# bf2_redraw.net
KiCad netlist of a schematic drawn in EAGLE
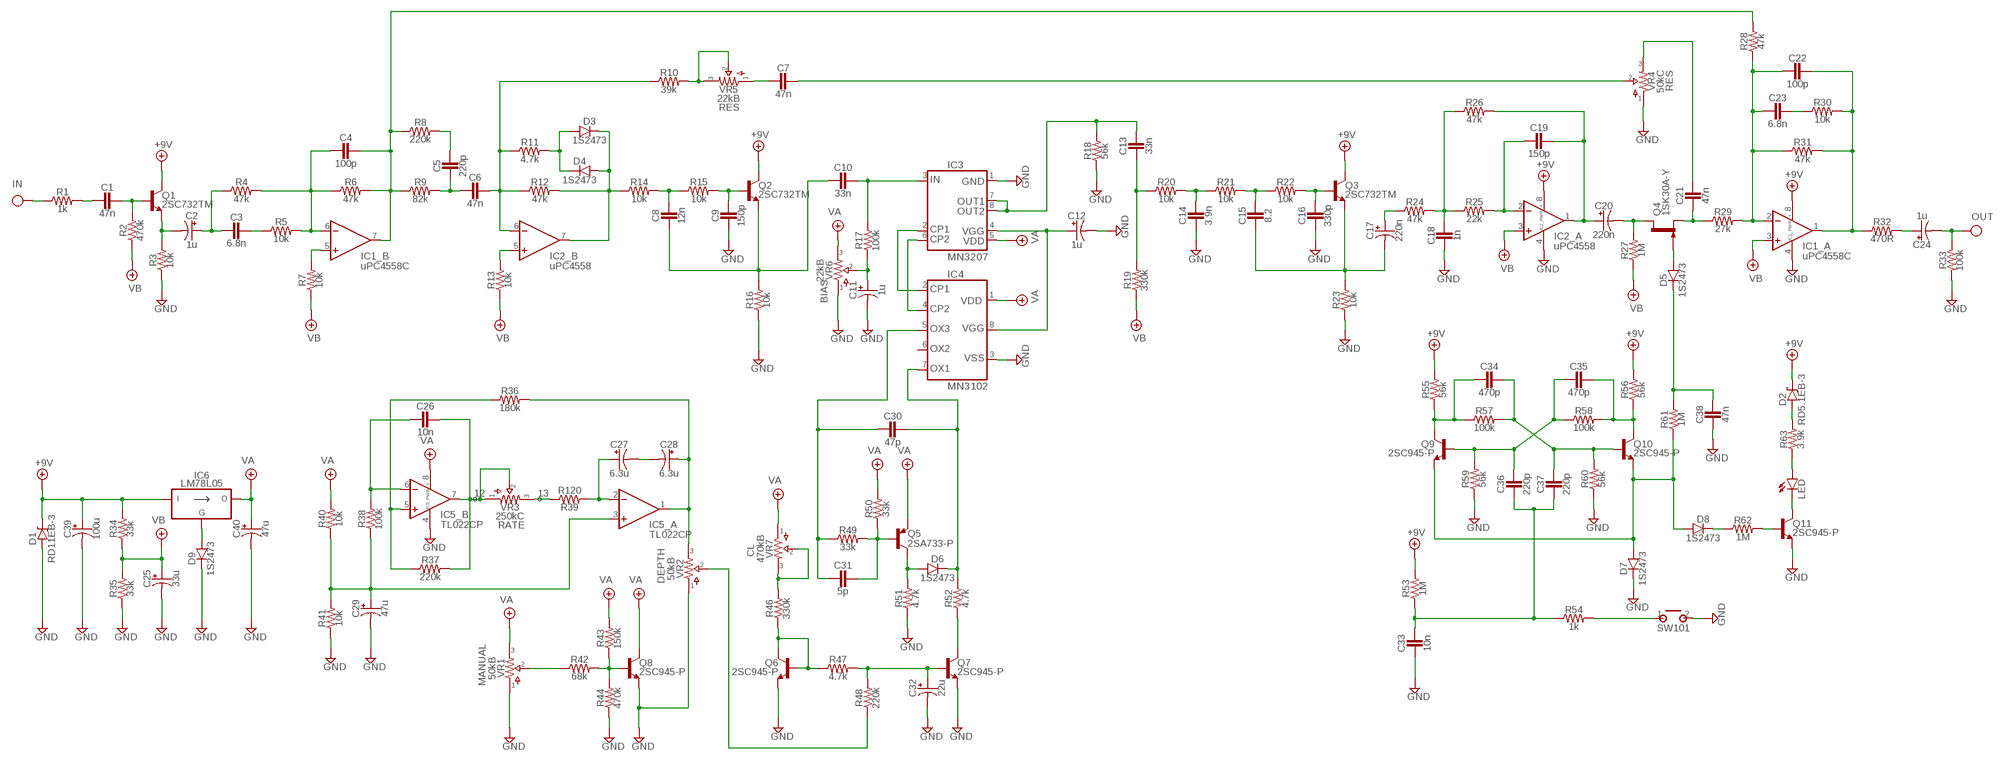
[diagram p0: schematic, sheet 1]

(export (version "E")
  (design (tool "Eeschema 10.0.6"))
  (components
    (comp (ref "C1")
      (value "47n")
      (footprint "eagle-import:BOX_SMALL")
      (libsource (lib "eagle-import") (part "CER/FILMBOX.1"))
    )
    (comp (ref "C2")
      (value "1u")
      (footprint "eagle-import:040_020")
      (libsource (lib "eagle-import") (part "0400"))
    )
    (comp (ref "C3")
      (value "6.8n")
      (footprint "eagle-import:BOX_SMALL")
      (libsource (lib "eagle-import") (part "CER/FILMBOX.1"))
    )
    (comp (ref "C4")
      (value "100p")
      (footprint "eagle-import:BOX_SMALL")
      (libsource (lib "eagle-import") (part "CER/FILMBOX.1"))
    )
    (comp (ref "C5")
      (value "220p")
      (footprint "eagle-import:BOX_SMALL")
      (libsource (lib "eagle-import") (part "CER/FILMBOX.1"))
    )
    (comp (ref "C6")
      (value "47n")
      (footprint "eagle-import:BOX_SMALL")
      (libsource (lib "eagle-import") (part "CER/FILMBOX.1"))
    )
    (comp (ref "C7")
      (value "47n")
      (footprint "eagle-import:BOX_SMALL")
      (libsource (lib "eagle-import") (part "CER/FILMBOX.1"))
    )
    (comp (ref "C8")
      (value "12n")
      (footprint "eagle-import:BOX_SMALL")
      (libsource (lib "eagle-import") (part "CER/FILMBOX.1"))
    )
    (comp (ref "C9")
      (value "150p")
      (footprint "eagle-import:BOX_SMALL")
      (libsource (lib "eagle-import") (part "CER/FILMBOX.1"))
    )
    (comp (ref "C10")
      (value "33n")
      (footprint "eagle-import:BOX_SMALL")
      (libsource (lib "eagle-import") (part "CER/FILMBOX.1"))
    )
    (comp (ref "C11")
      (value "1u")
      (footprint "eagle-import:040_020")
      (libsource (lib "eagle-import") (part "0400"))
    )
    (comp (ref "C12")
      (value "1u")
      (footprint "eagle-import:040_020")
      (libsource (lib "eagle-import") (part "0400"))
    )
    (comp (ref "C13")
      (value "33n")
      (footprint "eagle-import:BOX_SMALL")
      (libsource (lib "eagle-import") (part "CER/FILMBOX.1"))
    )
    (comp (ref "C14")
      (value "3.9n")
      (footprint "eagle-import:BOX_SMALL")
      (libsource (lib "eagle-import") (part "CER/FILMBOX.1"))
    )
    (comp (ref "C15")
      (value "8.2")
      (footprint "eagle-import:BOX_SMALL")
      (libsource (lib "eagle-import") (part "CER/FILMBOX.1"))
    )
    (comp (ref "C16")
      (value "330p")
      (footprint "eagle-import:BOX_SMALL")
      (libsource (lib "eagle-import") (part "CER/FILMBOX.1"))
    )
    (comp (ref "C17")
      (value "220n")
      (footprint "eagle-import:040_020")
      (libsource (lib "eagle-import") (part "0400"))
    )
    (comp (ref "C18")
      (value "1n")
      (footprint "eagle-import:BOX_SMALL")
      (libsource (lib "eagle-import") (part "CER/FILMBOX.1"))
    )
    (comp (ref "C19")
      (value "150p")
      (footprint "eagle-import:BOX_SMALL")
      (libsource (lib "eagle-import") (part "CER/FILMBOX.1"))
    )
    (comp (ref "C20")
      (value "220n")
      (footprint "eagle-import:040_020")
      (libsource (lib "eagle-import") (part "0400"))
    )
    (comp (ref "C21")
      (value "47n")
      (footprint "eagle-import:BOX_SMALL")
      (libsource (lib "eagle-import") (part "CER/FILMBOX.1"))
    )
    (comp (ref "C22")
      (value "100p")
      (footprint "eagle-import:BOX_SMALL")
      (libsource (lib "eagle-import") (part "CER/FILMBOX.1"))
    )
    (comp (ref "C23")
      (value "6.8n")
      (footprint "eagle-import:BOX_SMALL")
      (libsource (lib "eagle-import") (part "CER/FILMBOX.1"))
    )
    (comp (ref "C24")
      (value "1u")
      (footprint "eagle-import:040_020")
      (libsource (lib "eagle-import") (part "0400"))
    )
    (comp (ref "C25")
      (value "33u")
      (footprint "eagle-import:040_020")
      (libsource (lib "eagle-import") (part "0400"))
    )
    (comp (ref "C26")
      (value "10n")
      (footprint "eagle-import:BOX_SMALL")
      (libsource (lib "eagle-import") (part "CER/FILMBOX.1"))
    )
    (comp (ref "C27")
      (value "6.3u")
      (footprint "eagle-import:040_020")
      (libsource (lib "eagle-import") (part "0400"))
    )
    (comp (ref "C28")
      (value "6.3u")
      (footprint "eagle-import:040_020")
      (libsource (lib "eagle-import") (part "0400"))
    )
    (comp (ref "C29")
      (value "47u")
      (footprint "eagle-import:040_020")
      (libsource (lib "eagle-import") (part "0400"))
    )
    (comp (ref "C30")
      (value "47p")
      (footprint "eagle-import:BOX_SMALL")
      (libsource (lib "eagle-import") (part "CER/FILMBOX.1"))
    )
    (comp (ref "C31")
      (value "5p")
      (footprint "eagle-import:BOX_SMALL")
      (libsource (lib "eagle-import") (part "CER/FILMBOX.1"))
    )
    (comp (ref "C32")
      (value "22u")
      (footprint "eagle-import:040_020")
      (libsource (lib "eagle-import") (part "0400"))
    )
    (comp (ref "C33")
      (value "10n")
      (footprint "eagle-import:BOX_SMALL")
      (libsource (lib "eagle-import") (part "CER/FILMBOX.1"))
    )
    (comp (ref "C34")
      (value "470p")
      (footprint "eagle-import:BOX_SMALL")
      (libsource (lib "eagle-import") (part "CER/FILMBOX.1"))
    )
    (comp (ref "C35")
      (value "470p")
      (footprint "eagle-import:BOX_SMALL")
      (libsource (lib "eagle-import") (part "CER/FILMBOX.1"))
    )
    (comp (ref "C36")
      (value "220p")
      (footprint "eagle-import:BOX_SMALL")
      (libsource (lib "eagle-import") (part "CER/FILMBOX.1"))
    )
    (comp (ref "C37")
      (value "220p")
      (footprint "eagle-import:BOX_SMALL")
      (libsource (lib "eagle-import") (part "CER/FILMBOX.1"))
    )
    (comp (ref "C38")
      (value "47n")
      (footprint "eagle-import:BOX_SMALL")
      (libsource (lib "eagle-import") (part "CER/FILMBOX.1"))
    )
    (comp (ref "C39")
      (value "100u")
      (footprint "eagle-import:040_020")
      (libsource (lib "eagle-import") (part "0400"))
    )
    (comp (ref "C40")
      (value "47u")
      (footprint "eagle-import:040_020")
      (libsource (lib "eagle-import") (part "0400"))
    )
    (comp (ref "D1")
      (value "RD11EB-3")
      (footprint "eagle-import:DO41-2")
      (libsource (lib "eagle-import") (part "ZENER.2"))
    )
    (comp (ref "D2")
      (value "RD5.1EB-3")
      (footprint "eagle-import:DO41-2")
      (libsource (lib "eagle-import") (part "ZENER.2"))
    )
    (comp (ref "D3")
      (value "1S2473")
      (footprint "eagle-import:DO35-2")
      (libsource (lib "eagle-import") (part "DO35.2"))
    )
    (comp (ref "D4")
      (value "1S2473")
      (footprint "eagle-import:DO35-2")
      (libsource (lib "eagle-import") (part "DO35.2"))
    )
    (comp (ref "D5")
      (value "1S2473")
      (footprint "eagle-import:DO35-2")
      (libsource (lib "eagle-import") (part "DO35.2"))
    )
    (comp (ref "D6")
      (value "1S2473")
      (footprint "eagle-import:DO35-2")
      (libsource (lib "eagle-import") (part "DO35.2"))
    )
    (comp (ref "D7")
      (value "1S2473")
      (footprint "eagle-import:DO35-2")
      (libsource (lib "eagle-import") (part "DO35.2"))
    )
    (comp (ref "D8")
      (value "1S2473")
      (footprint "eagle-import:DO35-2")
      (libsource (lib "eagle-import") (part "DO35.2"))
    )
    (comp (ref "D9")
      (value "1S2473")
      (footprint "eagle-import:DO35-2")
      (libsource (lib "eagle-import") (part "DO35.2"))
    )
    (comp (ref "IC1")
      (value "uPC4558C")
      (footprint "eagle-import:DIL0")
      (libsource (lib "eagle-import") (part "DUALTH"))
    )
    (comp (ref "IC2")
      (value "uPC4558")
      (footprint "eagle-import:DIL0")
      (libsource (lib "eagle-import") (part "DUALTH"))
    )
    (comp (ref "IC3")
      (value "MN3207")
      (footprint "eagle-import:DIL0")
      (libsource (lib "eagle-import") (part "BL3208"))
    )
    (comp (ref "IC4")
      (value "MN3102")
      (footprint "eagle-import:DIL8")
      (libsource (lib "eagle-import") (part "CLOCK"))
    )
    (comp (ref "IC5")
      (value "TL022CP")
      (footprint "eagle-import:DIL0")
      (libsource (lib "eagle-import") (part "DUALTH"))
    )
    (comp (ref "IC6")
      (value "LM78L05")
      (footprint "eagle-import:TO92-")
      (libsource (lib "eagle-import") (part "LM78L05"))
    )
    (comp (ref "LED")
      (value "SLP1358")
      (footprint "eagle-import:3MM_D")
      (libsource (lib "eagle-import") (part "LED"))
    )
    (comp (ref "Q1")
      (value "2SC732TM")
      (footprint "eagle-import:TO92-")
      (libsource (lib "eagle-import") (part "2SC828A"))
    )
    (comp (ref "Q2")
      (value "2SC732TM")
      (footprint "eagle-import:TO92-")
      (libsource (lib "eagle-import") (part "2SC828A"))
    )
    (comp (ref "Q3")
      (value "2SC732TM")
      (footprint "eagle-import:TO92-")
      (libsource (lib "eagle-import") (part "2SC828A"))
    )
    (comp (ref "Q4")
      (value "1SK30A-Y")
      (footprint "eagle-import:TO92-")
      (libsource (lib "eagle-import") (part "2N3819TO-92S"))
    )
    (comp (ref "Q5")
      (value "2SA733-P")
      (footprint "eagle-import:TO92-")
      (libsource (lib "eagle-import") (part "2N3906-"))
    )
    (comp (ref "Q6")
      (value "2SC945-P")
      (footprint "eagle-import:TO92-")
      (libsource (lib "eagle-import") (part "2SC828A"))
    )
    (comp (ref "Q7")
      (value "2SC945-P")
      (footprint "eagle-import:TO92-")
      (libsource (lib "eagle-import") (part "2SC828A"))
    )
    (comp (ref "Q8")
      (value "2SC945-P")
      (footprint "eagle-import:TO92-")
      (libsource (lib "eagle-import") (part "2SC828A"))
    )
    (comp (ref "Q9")
      (value "2SC945-P")
      (footprint "eagle-import:TO92-")
      (libsource (lib "eagle-import") (part "2SC828A"))
    )
    (comp (ref "Q10")
      (value "2SC945-P")
      (footprint "eagle-import:TO92-")
      (libsource (lib "eagle-import") (part "2SC828A"))
    )
    (comp (ref "Q11")
      (value "2SC945-P")
      (footprint "eagle-import:TO92-")
      (libsource (lib "eagle-import") (part "2SC828A"))
    )
    (comp (ref "R1")
      (value "1k")
      (footprint "eagle-import:R0207_3")
      (libsource (lib "eagle-import") (part "R_.3B"))
    )
    (comp (ref "R2")
      (value "470k")
      (footprint "eagle-import:R0207_3")
      (libsource (lib "eagle-import") (part "R_.3B"))
    )
    (comp (ref "R3")
      (value "10k")
      (footprint "eagle-import:R0207_3")
      (libsource (lib "eagle-import") (part "R_.3B"))
    )
    (comp (ref "R4")
      (value "47k")
      (footprint "eagle-import:R0207_3")
      (libsource (lib "eagle-import") (part "R_.3B"))
    )
    (comp (ref "R5")
      (value "10k")
      (footprint "eagle-import:R0207_3")
      (libsource (lib "eagle-import") (part "R_.3B"))
    )
    (comp (ref "R6")
      (value "47k")
      (footprint "eagle-import:R0207_3")
      (libsource (lib "eagle-import") (part "R_.3B"))
    )
    (comp (ref "R7")
      (value "10k")
      (footprint "eagle-import:R0207_3")
      (libsource (lib "eagle-import") (part "R_.3B"))
    )
    (comp (ref "R8")
      (value "220k")
      (footprint "eagle-import:R0207_3")
      (libsource (lib "eagle-import") (part "R_.3B"))
    )
    (comp (ref "R9")
      (value "82k")
      (footprint "eagle-import:R0207_3")
      (libsource (lib "eagle-import") (part "R_.3B"))
    )
    (comp (ref "R10")
      (value "39k")
      (footprint "eagle-import:R0207_3")
      (libsource (lib "eagle-import") (part "R_.3B"))
    )
    (comp (ref "R11")
      (value "4.7k")
      (footprint "eagle-import:R0207_3")
      (libsource (lib "eagle-import") (part "R_.3B"))
    )
    (comp (ref "R12")
      (value "47k")
      (footprint "eagle-import:R0207_3")
      (libsource (lib "eagle-import") (part "R_.3B"))
    )
    (comp (ref "R13")
      (value "10k")
      (footprint "eagle-import:R0207_3")
      (libsource (lib "eagle-import") (part "R_.3B"))
    )
    (comp (ref "R14")
      (value "10k")
      (footprint "eagle-import:R0207_3")
      (libsource (lib "eagle-import") (part "R_.3B"))
    )
    (comp (ref "R15")
      (value "10k")
      (footprint "eagle-import:R0207_3")
      (libsource (lib "eagle-import") (part "R_.3B"))
    )
    (comp (ref "R16")
      (value "10k")
      (footprint "eagle-import:R0207_3")
      (libsource (lib "eagle-import") (part "R_.3B"))
    )
    (comp (ref "R17")
      (value "100k")
      (footprint "eagle-import:R0207_3")
      (libsource (lib "eagle-import") (part "R_.3B"))
    )
    (comp (ref "R18")
      (value "56k")
      (footprint "eagle-import:R0207_3")
      (libsource (lib "eagle-import") (part "R_.3B"))
    )
    (comp (ref "R19")
      (value "330k")
      (footprint "eagle-import:R0207_3")
      (libsource (lib "eagle-import") (part "R_.3B"))
    )
    (comp (ref "R20")
      (value "10k")
      (footprint "eagle-import:R0207_3")
      (libsource (lib "eagle-import") (part "R_.3B"))
    )
    (comp (ref "R21")
      (value "10k")
      (footprint "eagle-import:R0207_3")
      (libsource (lib "eagle-import") (part "R_.3B"))
    )
    (comp (ref "R22")
      (value "10k")
      (footprint "eagle-import:R0207_3")
      (libsource (lib "eagle-import") (part "R_.3B"))
    )
    (comp (ref "R23")
      (value "10k")
      (footprint "eagle-import:R0207_3")
      (libsource (lib "eagle-import") (part "R_.3B"))
    )
    (comp (ref "R24")
      (value "47k")
      (footprint "eagle-import:R0207_3")
      (libsource (lib "eagle-import") (part "R_.3B"))
    )
    (comp (ref "R25")
      (value "22k")
      (footprint "eagle-import:R0207_3")
      (libsource (lib "eagle-import") (part "R_.3B"))
    )
    (comp (ref "R26")
      (value "47k")
      (footprint "eagle-import:R0207_3")
      (libsource (lib "eagle-import") (part "R_.3B"))
    )
    (comp (ref "R27")
      (value "1M")
      (footprint "eagle-import:R0207_3")
      (libsource (lib "eagle-import") (part "R_.3B"))
    )
    (comp (ref "R28")
      (value "47k")
      (footprint "eagle-import:R0207_3")
      (libsource (lib "eagle-import") (part "R_.3B"))
    )
    (comp (ref "R29")
      (value "27k")
      (footprint "eagle-import:R0207_3")
      (libsource (lib "eagle-import") (part "R_.3B"))
    )
    (comp (ref "R30")
      (value "10k")
      (footprint "eagle-import:R0207_3")
      (libsource (lib "eagle-import") (part "R_.3B"))
    )
    (comp (ref "R31")
      (value "47k")
      (footprint "eagle-import:R0207_3")
      (libsource (lib "eagle-import") (part "R_.3B"))
    )
    (comp (ref "R32")
      (value "470R")
      (footprint "eagle-import:R0207_3")
      (libsource (lib "eagle-import") (part "R_.3B"))
    )
    (comp (ref "R33")
      (value "100k")
      (footprint "eagle-import:R0207_3")
      (libsource (lib "eagle-import") (part "R_.3B"))
    )
    (comp (ref "R34")
      (value "33k")
      (footprint "eagle-import:R0207_3")
      (libsource (lib "eagle-import") (part "R_.3B"))
    )
    (comp (ref "R35")
      (value "33k")
      (footprint "eagle-import:R0207_3")
      (libsource (lib "eagle-import") (part "R_.3B"))
    )
    (comp (ref "R36")
      (value "180k")
      (footprint "eagle-import:R0207_3")
      (libsource (lib "eagle-import") (part "R_.3B"))
    )
    (comp (ref "R37")
      (value "220k")
      (footprint "eagle-import:R0207_3")
      (libsource (lib "eagle-import") (part "R_.3B"))
    )
    (comp (ref "R38")
      (value "100k")
      (footprint "eagle-import:R0207_3")
      (libsource (lib "eagle-import") (part "R_.3B"))
    )
    (comp (ref "R40")
      (value "10k")
      (footprint "eagle-import:R0207_3")
      (libsource (lib "eagle-import") (part "R_.3B"))
    )
    (comp (ref "R41")
      (value "10k")
      (footprint "eagle-import:R0207_3")
      (libsource (lib "eagle-import") (part "R_.3B"))
    )
    (comp (ref "R42")
      (value "68k")
      (footprint "eagle-import:R0207_3")
      (libsource (lib "eagle-import") (part "R_.3B"))
    )
    (comp (ref "R43")
      (value "150k")
      (footprint "eagle-import:R0207_3")
      (libsource (lib "eagle-import") (part "R_.3B"))
    )
    (comp (ref "R44")
      (value "470k")
      (footprint "eagle-import:R0207_3")
      (libsource (lib "eagle-import") (part "R_.3B"))
    )
    (comp (ref "R46")
      (value "330k")
      (footprint "eagle-import:R0207_3")
      (libsource (lib "eagle-import") (part "R_.3B"))
    )
    (comp (ref "R47")
      (value "4.7k")
      (footprint "eagle-import:R0207_3")
      (libsource (lib "eagle-import") (part "R_.3B"))
    )
    (comp (ref "R48")
      (value "220k")
      (footprint "eagle-import:R0207_3")
      (libsource (lib "eagle-import") (part "R_.3B"))
    )
    (comp (ref "R49")
      (value "33k")
      (footprint "eagle-import:R0207_3")
      (libsource (lib "eagle-import") (part "R_.3B"))
    )
    (comp (ref "R50")
      (value "33k")
      (footprint "eagle-import:R0207_3")
      (libsource (lib "eagle-import") (part "R_.3B"))
    )
    (comp (ref "R51")
      (value "4.7k")
      (footprint "eagle-import:R0207_3")
      (libsource (lib "eagle-import") (part "R_.3B"))
    )
    (comp (ref "R52")
      (value "4.7k")
      (footprint "eagle-import:R0207_3")
      (libsource (lib "eagle-import") (part "R_.3B"))
    )
    (comp (ref "R53")
      (value "1M")
      (footprint "eagle-import:R0207_3")
      (libsource (lib "eagle-import") (part "R_.3B"))
    )
    (comp (ref "R54")
      (value "1k")
      (footprint "eagle-import:R0207_3")
      (libsource (lib "eagle-import") (part "R_.3B"))
    )
    (comp (ref "R55")
      (value "56k")
      (footprint "eagle-import:R0207_3")
      (libsource (lib "eagle-import") (part "R_.3B"))
    )
    (comp (ref "R56")
      (value "56k")
      (footprint "eagle-import:R0207_3")
      (libsource (lib "eagle-import") (part "R_.3B"))
    )
    (comp (ref "R57")
      (value "100k")
      (footprint "eagle-import:R0207_3")
      (libsource (lib "eagle-import") (part "R_.3B"))
    )
    (comp (ref "R58")
      (value "100k")
      (footprint "eagle-import:R0207_3")
      (libsource (lib "eagle-import") (part "R_.3B"))
    )
    (comp (ref "R59")
      (value "56k")
      (footprint "eagle-import:R0207_3")
      (libsource (lib "eagle-import") (part "R_.3B"))
    )
    (comp (ref "R60")
      (value "56k")
      (footprint "eagle-import:R0207_3")
      (libsource (lib "eagle-import") (part "R_.3B"))
    )
    (comp (ref "R61")
      (value "1M")
      (footprint "eagle-import:R0207_3")
      (libsource (lib "eagle-import") (part "R_.3B"))
    )
    (comp (ref "R62")
      (value "1M")
      (footprint "eagle-import:R0207_3")
      (libsource (lib "eagle-import") (part "R_.3B"))
    )
    (comp (ref "R63")
      (value "3.9k")
      (footprint "eagle-import:R0207_3")
      (libsource (lib "eagle-import") (part "R_.3B"))
    )
    (comp (ref "R120")
      (value "R39")
      (footprint "eagle-import:R0207_3")
      (libsource (lib "eagle-import") (part "R_.3B"))
    )
    (comp (ref "SW101")
      (value "MOMENTARY")
      (footprint "eagle-import:SPST")
      (libsource (lib "eagle-import") (part "MOMENTARY"))
    )
    (comp (ref "VR1")
      (value "50kB")
      (footprint "eagle-import:16MM")
      (libsource (lib "eagle-import") (part "POTS16MM"))
    )
    (comp (ref "VR2")
      (value "50kB")
      (footprint "eagle-import:16MM")
      (libsource (lib "eagle-import") (part "POTS16MM"))
    )
    (comp (ref "VR3")
      (value "250kC")
      (footprint "eagle-import:16MM")
      (libsource (lib "eagle-import") (part "POTS16MM"))
    )
    (comp (ref "VR4")
      (value "50kC")
      (footprint "eagle-import:16MM")
      (libsource (lib "eagle-import") (part "POTS16MM"))
    )
    (comp (ref "VR5")
      (value "22kB")
      (footprint "eagle-import:16MM")
      (libsource (lib "eagle-import") (part "POTS16MM"))
    )
    (comp (ref "VR6")
      (value "22kB")
      (footprint "eagle-import:16MM")
      (libsource (lib "eagle-import") (part "POTS16MM"))
    )
    (comp (ref "VR7")
      (value "470kB")
      (footprint "eagle-import:16MM")
      (libsource (lib "eagle-import") (part "POTS16MM"))
    )
  )
  (nets
    (net (code "1") (name "+9V") (class "Default")
      (node (ref "C39") (pin "+") (pinfunction "+_+") (pintype "passive"))
      (node (ref "D1") (pin "C") (pinfunction "C_C") (pintype "passive"))
      (node (ref "D2") (pin "C") (pinfunction "C_C") (pintype "passive"))
      (node (ref "IC1") (pin "8") (pinfunction "V+_8") (pintype "power_in"))
      (node (ref "IC2") (pin "8") (pinfunction "V+_8") (pintype "power_in"))
      (node (ref "IC6") (pin "1") (pinfunction "VI_1") (pintype "input"))
      (node (ref "Q1") (pin "2") (pinfunction "C_2") (pintype "passive"))
      (node (ref "Q2") (pin "2") (pinfunction "C_2") (pintype "passive"))
      (node (ref "Q3") (pin "2") (pinfunction "C_2") (pintype "passive"))
      (node (ref "R34") (pin "2") (pinfunction "2_2") (pintype "passive"))
      (node (ref "R53") (pin "2") (pinfunction "2_2") (pintype "passive"))
      (node (ref "R55") (pin "2") (pinfunction "2_2") (pintype "passive"))
      (node (ref "R56") (pin "2") (pinfunction "2_2") (pintype "passive"))
    )
    (net (code "2") (name "GND") (class "Default")
      (node (ref "C11") (pin "-") (pinfunction "-_-") (pintype "passive"))
      (node (ref "C12") (pin "-") (pinfunction "-_-") (pintype "passive"))
      (node (ref "C14") (pin "2") (pinfunction "2_2") (pintype "passive"))
      (node (ref "C16") (pin "2") (pinfunction "2_2") (pintype "passive"))
      (node (ref "C18") (pin "2") (pinfunction "2_2") (pintype "passive"))
      (node (ref "C25") (pin "-") (pinfunction "-_-") (pintype "passive"))
      (node (ref "C29") (pin "-") (pinfunction "-_-") (pintype "passive"))
      (node (ref "C32") (pin "-") (pinfunction "-_-") (pintype "passive"))
      (node (ref "C33") (pin "2") (pinfunction "2_2") (pintype "passive"))
      (node (ref "C38") (pin "2") (pinfunction "2_2") (pintype "passive"))
      (node (ref "C39") (pin "-") (pinfunction "-_-") (pintype "passive"))
      (node (ref "C40") (pin "-") (pinfunction "-_-") (pintype "passive"))
      (node (ref "C9") (pin "2") (pinfunction "2_2") (pintype "passive"))
      (node (ref "D1") (pin "A") (pinfunction "A_A") (pintype "passive"))
      (node (ref "D7") (pin "C") (pinfunction "C_C") (pintype "passive"))
      (node (ref "D9") (pin "C") (pinfunction "C_C") (pintype "passive"))
      (node (ref "IC1") (pin "4") (pinfunction "V-_4") (pintype "power_in"))
      (node (ref "IC2") (pin "4") (pinfunction "V-_4") (pintype "power_in"))
      (node (ref "IC3") (pin "1") (pinfunction "1_1") (pintype "bidirectional"))
      (node (ref "IC4") (pin "3") (pinfunction "P$3_3") (pintype "bidirectional"))
      (node (ref "IC5") (pin "4") (pinfunction "V-_4") (pintype "power_in"))
      (node (ref "Q11") (pin "3") (pinfunction "E_3") (pintype "passive"))
      (node (ref "Q6") (pin "3") (pinfunction "E_3") (pintype "passive"))
      (node (ref "Q7") (pin "3") (pinfunction "E_3") (pintype "passive"))
      (node (ref "Q8") (pin "3") (pinfunction "E_3") (pintype "passive"))
      (node (ref "R16") (pin "1") (pinfunction "1_1") (pintype "passive"))
      (node (ref "R18") (pin "1") (pinfunction "1_1") (pintype "passive"))
      (node (ref "R23") (pin "1") (pinfunction "1_1") (pintype "passive"))
      (node (ref "R3") (pin "1") (pinfunction "1_1") (pintype "passive"))
      (node (ref "R33") (pin "2") (pinfunction "2_2") (pintype "passive"))
      (node (ref "R35") (pin "1") (pinfunction "1_1") (pintype "passive"))
      (node (ref "R41") (pin "1") (pinfunction "1_1") (pintype "passive"))
      (node (ref "R44") (pin "1") (pinfunction "1_1") (pintype "passive"))
      (node (ref "R51") (pin "1") (pinfunction "1_1") (pintype "passive"))
      (node (ref "R59") (pin "1") (pinfunction "1_1") (pintype "passive"))
      (node (ref "R60") (pin "1") (pinfunction "1_1") (pintype "passive"))
      (node (ref "SW101") (pin "2") (pinfunction "S_2") (pintype "passive"))
      (node (ref "VR1") (pin "1") (pinfunction "1_1") (pintype "passive"))
      (node (ref "VR2") (pin "1") (pinfunction "1_1") (pintype "passive"))
      (node (ref "VR4") (pin "1") (pinfunction "1_1") (pintype "passive"))
      (node (ref "VR6") (pin "1") (pinfunction "1_1") (pintype "passive"))
    )
    (net (code "3") (name "IN") (class "Default")
      (node (ref "R1") (pin "1") (pinfunction "1_1") (pintype "passive"))
    )
    (net (code "4") (name "Net-(C1-Pad2)") (class "Default")
      (node (ref "C1") (pin "2") (pinfunction "2_2") (pintype "passive"))
      (node (ref "R1") (pin "2") (pinfunction "2_2") (pintype "passive"))
    )
    (net (code "5") (name "Net-(C2-Pad+)") (class "Default")
      (node (ref "C2") (pin "+") (pinfunction "+_+") (pintype "passive"))
      (node (ref "C3") (pin "2") (pinfunction "2_2") (pintype "passive"))
      (node (ref "R4") (pin "1") (pinfunction "1_1") (pintype "passive"))
    )
    (net (code "6") (name "Net-(C3-Pad1)") (class "Default")
      (node (ref "C3") (pin "1") (pinfunction "1_1") (pintype "passive"))
      (node (ref "R5") (pin "1") (pinfunction "1_1") (pintype "passive"))
    )
    (net (code "7") (name "Net-(C5-Pad1)") (class "Default")
      (node (ref "C5") (pin "1") (pinfunction "1_1") (pintype "passive"))
      (node (ref "R8") (pin "2") (pinfunction "2_2") (pintype "passive"))
    )
    (net (code "8") (name "Net-(C5-Pad2)") (class "Default")
      (node (ref "C5") (pin "2") (pinfunction "2_2") (pintype "passive"))
      (node (ref "C6") (pin "2") (pinfunction "2_2") (pintype "passive"))
      (node (ref "R9") (pin "2") (pinfunction "2_2") (pintype "passive"))
    )
    (net (code "9") (name "Net-(C7-Pad1)") (class "Default")
      (node (ref "C7") (pin "1") (pinfunction "1_1") (pintype "passive"))
      (node (ref "VR4") (pin "2") (pinfunction "2_2") (pintype "passive"))
    )
    (net (code "10") (name "Net-(C7-Pad2)") (class "Default")
      (node (ref "C7") (pin "2") (pinfunction "2_2") (pintype "passive"))
      (node (ref "VR5") (pin "1") (pinfunction "1_1") (pintype "passive"))
    )
    (net (code "11") (name "Net-(C8-Pad1)") (class "Default")
      (node (ref "C8") (pin "1") (pinfunction "1_1") (pintype "passive"))
      (node (ref "R14") (pin "2") (pinfunction "2_2") (pintype "passive"))
      (node (ref "R15") (pin "1") (pinfunction "1_1") (pintype "passive"))
    )
    (net (code "12") (name "Net-(C10-Pad1)") (class "Default")
      (node (ref "C10") (pin "1") (pinfunction "1_1") (pintype "passive"))
      (node (ref "IC3") (pin "3") (pinfunction "3_3") (pintype "bidirectional"))
      (node (ref "R17") (pin "2") (pinfunction "2_2") (pintype "passive"))
    )
    (net (code "13") (name "Net-(C11-Pad+)") (class "Default")
      (node (ref "C11") (pin "+") (pinfunction "+_+") (pintype "passive"))
      (node (ref "R17") (pin "1") (pinfunction "1_1") (pintype "passive"))
      (node (ref "VR6") (pin "2") (pinfunction "2_2") (pintype "passive"))
    )
    (net (code "14") (name "Net-(C13-Pad1)") (class "Default")
      (node (ref "C13") (pin "1") (pinfunction "1_1") (pintype "passive"))
      (node (ref "IC3") (pin "7") (pinfunction "7_7") (pintype "bidirectional"))
      (node (ref "IC3") (pin "8") (pinfunction "8_8") (pintype "bidirectional"))
      (node (ref "R18") (pin "2") (pinfunction "2_2") (pintype "passive"))
    )
    (net (code "15") (name "Net-(C13-Pad2)") (class "Default")
      (node (ref "C13") (pin "2") (pinfunction "2_2") (pintype "passive"))
      (node (ref "R19") (pin "2") (pinfunction "2_2") (pintype "passive"))
      (node (ref "R20") (pin "1") (pinfunction "1_1") (pintype "passive"))
    )
    (net (code "16") (name "Net-(C14-Pad1)") (class "Default")
      (node (ref "C14") (pin "1") (pinfunction "1_1") (pintype "passive"))
      (node (ref "R20") (pin "2") (pinfunction "2_2") (pintype "passive"))
      (node (ref "R21") (pin "1") (pinfunction "1_1") (pintype "passive"))
    )
    (net (code "17") (name "Net-(C15-Pad1)") (class "Default")
      (node (ref "C15") (pin "1") (pinfunction "1_1") (pintype "passive"))
      (node (ref "R21") (pin "2") (pinfunction "2_2") (pintype "passive"))
      (node (ref "R22") (pin "1") (pinfunction "1_1") (pintype "passive"))
    )
    (net (code "18") (name "Net-(C17-Pad+)") (class "Default")
      (node (ref "C17") (pin "+") (pinfunction "+_+") (pintype "passive"))
      (node (ref "R24") (pin "1") (pinfunction "1_1") (pintype "passive"))
    )
    (net (code "19") (name "Net-(C18-Pad1)") (class "Default")
      (node (ref "C18") (pin "1") (pinfunction "1_1") (pintype "passive"))
      (node (ref "R24") (pin "2") (pinfunction "2_2") (pintype "passive"))
      (node (ref "R25") (pin "1") (pinfunction "1_1") (pintype "passive"))
      (node (ref "R26") (pin "1") (pinfunction "1_1") (pintype "passive"))
    )
    (net (code "20") (name "Net-(C21-Pad1)") (class "Default")
      (node (ref "C21") (pin "1") (pinfunction "1_1") (pintype "passive"))
      (node (ref "VR4") (pin "3") (pinfunction "3_3") (pintype "passive"))
    )
    (net (code "21") (name "Net-(C23-Pad1)") (class "Default")
      (node (ref "C23") (pin "1") (pinfunction "1_1") (pintype "passive"))
      (node (ref "R30") (pin "1") (pinfunction "1_1") (pintype "passive"))
    )
    (net (code "22") (name "Net-(C24-Pad+)") (class "Default")
      (node (ref "C24") (pin "+") (pinfunction "+_+") (pintype "passive"))
      (node (ref "R32") (pin "2") (pinfunction "2_2") (pintype "passive"))
    )
    (net (code "23") (name "Net-(C27-Pad-)") (class "Default")
      (node (ref "C27") (pin "-") (pinfunction "-_-") (pintype "passive"))
      (node (ref "C28") (pin "-") (pinfunction "-_-") (pintype "passive"))
    )
    (net (code "24") (name "Net-(C33-Pad1)") (class "Default")
      (node (ref "C33") (pin "1") (pinfunction "1_1") (pintype "passive"))
      (node (ref "C36") (pin "2") (pinfunction "2_2") (pintype "passive"))
      (node (ref "C37") (pin "2") (pinfunction "2_2") (pintype "passive"))
      (node (ref "R53") (pin "1") (pinfunction "1_1") (pintype "passive"))
      (node (ref "R54") (pin "1") (pinfunction "1_1") (pintype "passive"))
    )
    (net (code "25") (name "Net-(C38-Pad1)") (class "Default")
      (node (ref "C38") (pin "1") (pinfunction "1_1") (pintype "passive"))
      (node (ref "D5") (pin "C") (pinfunction "C_C") (pintype "passive"))
      (node (ref "R61") (pin "2") (pinfunction "2_2") (pintype "passive"))
    )
    (net (code "26") (name "Net-(D2-PadA)") (class "Default")
      (node (ref "D2") (pin "A") (pinfunction "A_A") (pintype "passive"))
      (node (ref "R63") (pin "2") (pinfunction "2_2") (pintype "passive"))
    )
    (net (code "27") (name "Net-(D3-PadA)") (class "Default")
      (node (ref "D3") (pin "A") (pinfunction "A_A") (pintype "passive"))
      (node (ref "D4") (pin "C") (pinfunction "C_C") (pintype "passive"))
      (node (ref "R11") (pin "2") (pinfunction "2_2") (pintype "passive"))
    )
    (net (code "28") (name "Net-(D8-PadC)") (class "Default")
      (node (ref "D8") (pin "C") (pinfunction "C_C") (pintype "passive"))
      (node (ref "R62") (pin "1") (pinfunction "1_1") (pintype "passive"))
    )
    (net (code "29") (name "Net-(IC1A--IN)") (class "Default")
      (node (ref "C22") (pin "2") (pinfunction "2_2") (pintype "passive"))
      (node (ref "C23") (pin "2") (pinfunction "2_2") (pintype "passive"))
      (node (ref "IC1") (pin "2") (pinfunction "-IN_2") (pintype "input"))
      (node (ref "R28") (pin "1") (pinfunction "1_1") (pintype "passive"))
      (node (ref "R29") (pin "2") (pinfunction "2_2") (pintype "passive"))
      (node (ref "R31") (pin "1") (pinfunction "1_1") (pintype "passive"))
    )
    (net (code "30") (name "Net-(IC1A-OUT)") (class "Default")
      (node (ref "C22") (pin "1") (pinfunction "1_1") (pintype "passive"))
      (node (ref "IC1") (pin "1") (pinfunction "OUT_1") (pintype "output"))
      (node (ref "R30") (pin "2") (pinfunction "2_2") (pintype "passive"))
      (node (ref "R31") (pin "2") (pinfunction "2_2") (pintype "passive"))
      (node (ref "R32") (pin "1") (pinfunction "1_1") (pintype "passive"))
    )
    (net (code "31") (name "Net-(IC1B-+IN)") (class "Default")
      (node (ref "IC1") (pin "5") (pinfunction "+IN_5") (pintype "input"))
      (node (ref "R7") (pin "2") (pinfunction "2_2") (pintype "passive"))
    )
    (net (code "32") (name "Net-(IC1B--IN)") (class "Default")
      (node (ref "C4") (pin "2") (pinfunction "2_2") (pintype "passive"))
      (node (ref "IC1") (pin "6") (pinfunction "-IN_6") (pintype "input"))
      (node (ref "R4") (pin "2") (pinfunction "2_2") (pintype "passive"))
      (node (ref "R5") (pin "2") (pinfunction "2_2") (pintype "passive"))
      (node (ref "R6") (pin "1") (pinfunction "1_1") (pintype "passive"))
    )
    (net (code "33") (name "Net-(IC1B-OUT)") (class "Default")
      (node (ref "C4") (pin "1") (pinfunction "1_1") (pintype "passive"))
      (node (ref "IC1") (pin "7") (pinfunction "OUT_7") (pintype "output"))
      (node (ref "R28") (pin "2") (pinfunction "2_2") (pintype "passive"))
      (node (ref "R6") (pin "2") (pinfunction "2_2") (pintype "passive"))
      (node (ref "R8") (pin "1") (pinfunction "1_1") (pintype "passive"))
      (node (ref "R9") (pin "1") (pinfunction "1_1") (pintype "passive"))
    )
    (net (code "34") (name "Net-(IC2A--IN)") (class "Default")
      (node (ref "C19") (pin "2") (pinfunction "2_2") (pintype "passive"))
      (node (ref "IC2") (pin "2") (pinfunction "-IN_2") (pintype "input"))
      (node (ref "R25") (pin "2") (pinfunction "2_2") (pintype "passive"))
    )
    (net (code "35") (name "Net-(IC2A-OUT)") (class "Default")
      (node (ref "C19") (pin "1") (pinfunction "1_1") (pintype "passive"))
      (node (ref "C20") (pin "+") (pinfunction "+_+") (pintype "passive"))
      (node (ref "IC2") (pin "1") (pinfunction "OUT_1") (pintype "output"))
      (node (ref "R26") (pin "2") (pinfunction "2_2") (pintype "passive"))
    )
    (net (code "36") (name "Net-(IC2B-+IN)") (class "Default")
      (node (ref "IC2") (pin "5") (pinfunction "+IN_5") (pintype "input"))
      (node (ref "R13") (pin "2") (pinfunction "2_2") (pintype "passive"))
    )
    (net (code "37") (name "Net-(IC2B--IN)") (class "Default")
      (node (ref "C6") (pin "1") (pinfunction "1_1") (pintype "passive"))
      (node (ref "IC2") (pin "6") (pinfunction "-IN_6") (pintype "input"))
      (node (ref "R10") (pin "1") (pinfunction "1_1") (pintype "passive"))
      (node (ref "R11") (pin "1") (pinfunction "1_1") (pintype "passive"))
      (node (ref "R12") (pin "1") (pinfunction "1_1") (pintype "passive"))
    )
    (net (code "38") (name "Net-(IC2B-OUT)") (class "Default")
      (node (ref "D3") (pin "C") (pinfunction "C_C") (pintype "passive"))
      (node (ref "D4") (pin "A") (pinfunction "A_A") (pintype "passive"))
      (node (ref "IC2") (pin "7") (pinfunction "OUT_7") (pintype "output"))
      (node (ref "R12") (pin "2") (pinfunction "2_2") (pintype "passive"))
      (node (ref "R14") (pin "1") (pinfunction "1_1") (pintype "passive"))
    )
    (net (code "39") (name "Net-(IC4-P$2)") (class "Default")
      (node (ref "IC3") (pin "2") (pinfunction "2_2") (pintype "bidirectional"))
      (node (ref "IC4") (pin "2") (pinfunction "P$2_2") (pintype "bidirectional"))
    )
    (net (code "40") (name "Net-(IC4-P$4)") (class "Default")
      (node (ref "IC3") (pin "6") (pinfunction "6_6") (pintype "bidirectional"))
      (node (ref "IC4") (pin "4") (pinfunction "P$4_4") (pintype "bidirectional"))
    )
    (net (code "41") (name "Net-(IC4-P$5)") (class "Default")
      (node (ref "C30") (pin "2") (pinfunction "2_2") (pintype "passive"))
      (node (ref "C31") (pin "2") (pinfunction "2_2") (pintype "passive"))
      (node (ref "IC4") (pin "5") (pinfunction "P$5_5") (pintype "bidirectional"))
      (node (ref "R49") (pin "1") (pinfunction "1_1") (pintype "passive"))
    )
    (net (code "42") (name "Net-(IC4-P$7)") (class "Default")
      (node (ref "C30") (pin "1") (pinfunction "1_1") (pintype "passive"))
      (node (ref "D6") (pin "C") (pinfunction "C_C") (pintype "passive"))
      (node (ref "IC4") (pin "7") (pinfunction "P$7_7") (pintype "bidirectional"))
      (node (ref "R52") (pin "2") (pinfunction "2_2") (pintype "passive"))
    )
    (net (code "43") (name "Net-(IC4-P$8)") (class "Default")
      (node (ref "C12") (pin "+") (pinfunction "+_+") (pintype "passive"))
      (node (ref "IC3") (pin "4") (pinfunction "4_4") (pintype "bidirectional"))
      (node (ref "IC4") (pin "8") (pinfunction "P$8_8") (pintype "bidirectional"))
    )
    (net (code "44") (name "Net-(IC5A-+IN)") (class "Default")
      (node (ref "C29") (pin "+") (pinfunction "+_+") (pintype "passive"))
      (node (ref "IC5") (pin "3") (pinfunction "+IN_3") (pintype "input"))
      (node (ref "R38") (pin "1") (pinfunction "1_1") (pintype "passive"))
      (node (ref "R40") (pin "1") (pinfunction "1_1") (pintype "passive"))
      (node (ref "R41") (pin "2") (pinfunction "2_2") (pintype "passive"))
    )
    (net (code "45") (name "Net-(IC5A--IN)") (class "Default")
      (node (ref "C27") (pin "+") (pinfunction "+_+") (pintype "passive"))
      (node (ref "IC5") (pin "2") (pinfunction "-IN_2") (pintype "input"))
      (node (ref "R120") (pin "2") (pinfunction "2_2") (pintype "passive"))
    )
    (net (code "46") (name "Net-(IC5A-OUT)") (class "Default")
      (node (ref "C28") (pin "+") (pinfunction "+_+") (pintype "passive"))
      (node (ref "IC5") (pin "1") (pinfunction "OUT_1") (pintype "output"))
      (node (ref "R36") (pin "2") (pinfunction "2_2") (pintype "passive"))
      (node (ref "VR2") (pin "3") (pinfunction "3_3") (pintype "passive"))
    )
    (net (code "47") (name "Net-(IC5B-+IN)") (class "Default")
      (node (ref "IC5") (pin "5") (pinfunction "+IN_5") (pintype "input"))
      (node (ref "R36") (pin "1") (pinfunction "1_1") (pintype "passive"))
      (node (ref "R37") (pin "1") (pinfunction "1_1") (pintype "passive"))
    )
    (net (code "48") (name "Net-(IC5B--IN)") (class "Default")
      (node (ref "C26") (pin "2") (pinfunction "2_2") (pintype "passive"))
      (node (ref "IC5") (pin "6") (pinfunction "-IN_6") (pintype "input"))
      (node (ref "R38") (pin "2") (pinfunction "2_2") (pintype "passive"))
    )
    (net (code "49") (name "Net-(IC5B-OUT)") (class "Default")
      (node (ref "C26") (pin "1") (pinfunction "1_1") (pintype "passive"))
      (node (ref "IC5") (pin "7") (pinfunction "OUT_7") (pintype "output"))
      (node (ref "R37") (pin "2") (pinfunction "2_2") (pintype "passive"))
      (node (ref "VR3") (pin "1") (pinfunction "1_1") (pintype "passive"))
      (node (ref "VR3") (pin "2") (pinfunction "2_2") (pintype "passive"))
    )
    (net (code "50") (name "Net-(IC6-GND)") (class "Default")
      (node (ref "D9") (pin "A") (pinfunction "A_A") (pintype "passive"))
      (node (ref "IC6") (pin "2") (pinfunction "GND_2") (pintype "passive"))
    )
    (net (code "51") (name "Net-(LED-A)") (class "Default")
      (node (ref "LED") (pin "ANODE") (pinfunction "A_ANODE") (pintype "passive"))
      (node (ref "R63") (pin "1") (pinfunction "1_1") (pintype "passive"))
    )
    (net (code "52") (name "Net-(LED-C)") (class "Default")
      (node (ref "LED") (pin "P$1") (pinfunction "C_P$1") (pintype "passive"))
      (node (ref "Q11") (pin "2") (pinfunction "C_2") (pintype "passive"))
    )
    (net (code "53") (name "Net-(Q1-B)") (class "Default")
      (node (ref "C1") (pin "1") (pinfunction "1_1") (pintype "passive"))
      (node (ref "Q1") (pin "1") (pinfunction "B_1") (pintype "passive"))
      (node (ref "R2") (pin "2") (pinfunction "2_2") (pintype "passive"))
    )
    (net (code "54") (name "Net-(Q1-E)") (class "Default")
      (node (ref "C2") (pin "-") (pinfunction "-_-") (pintype "passive"))
      (node (ref "Q1") (pin "3") (pinfunction "E_3") (pintype "passive"))
      (node (ref "R3") (pin "2") (pinfunction "2_2") (pintype "passive"))
    )
    (net (code "55") (name "Net-(Q2-B)") (class "Default")
      (node (ref "C9") (pin "1") (pinfunction "1_1") (pintype "passive"))
      (node (ref "Q2") (pin "1") (pinfunction "B_1") (pintype "passive"))
      (node (ref "R15") (pin "2") (pinfunction "2_2") (pintype "passive"))
    )
    (net (code "56") (name "Net-(Q2-E)") (class "Default")
      (node (ref "C10") (pin "2") (pinfunction "2_2") (pintype "passive"))
      (node (ref "C8") (pin "2") (pinfunction "2_2") (pintype "passive"))
      (node (ref "Q2") (pin "3") (pinfunction "E_3") (pintype "passive"))
      (node (ref "R16") (pin "2") (pinfunction "2_2") (pintype "passive"))
    )
    (net (code "57") (name "Net-(Q3-B)") (class "Default")
      (node (ref "C16") (pin "1") (pinfunction "1_1") (pintype "passive"))
      (node (ref "Q3") (pin "1") (pinfunction "B_1") (pintype "passive"))
      (node (ref "R22") (pin "2") (pinfunction "2_2") (pintype "passive"))
    )
    (net (code "58") (name "Net-(Q3-E)") (class "Default")
      (node (ref "C15") (pin "2") (pinfunction "2_2") (pintype "passive"))
      (node (ref "C17") (pin "-") (pinfunction "-_-") (pintype "passive"))
      (node (ref "Q3") (pin "3") (pinfunction "E_3") (pintype "passive"))
      (node (ref "R23") (pin "2") (pinfunction "2_2") (pintype "passive"))
    )
    (net (code "59") (name "Net-(Q4-D)") (class "Default")
      (node (ref "C20") (pin "-") (pinfunction "-_-") (pintype "passive"))
      (node (ref "Q4") (pin "3") (pinfunction "D_3") (pintype "passive"))
      (node (ref "R27") (pin "2") (pinfunction "2_2") (pintype "passive"))
    )
    (net (code "60") (name "Net-(Q4-G)") (class "Default")
      (node (ref "D5") (pin "A") (pinfunction "A_A") (pintype "passive"))
      (node (ref "Q4") (pin "2") (pinfunction "G_2") (pintype "passive"))
    )
    (net (code "61") (name "Net-(Q4-S)") (class "Default")
      (node (ref "C21") (pin "2") (pinfunction "2_2") (pintype "passive"))
      (node (ref "Q4") (pin "1") (pinfunction "S_1") (pintype "passive"))
      (node (ref "R29") (pin "1") (pinfunction "1_1") (pintype "passive"))
    )
    (net (code "62") (name "Net-(Q5-B)") (class "Default")
      (node (ref "C31") (pin "1") (pinfunction "1_1") (pintype "passive"))
      (node (ref "Q5") (pin "2") (pinfunction "B_2") (pintype "passive"))
      (node (ref "R49") (pin "2") (pinfunction "2_2") (pintype "passive"))
      (node (ref "R50") (pin "1") (pinfunction "1_1") (pintype "passive"))
    )
    (net (code "63") (name "Net-(Q5-C)") (class "Default")
      (node (ref "D6") (pin "A") (pinfunction "A_A") (pintype "passive"))
      (node (ref "Q5") (pin "1") (pinfunction "C_1") (pintype "passive"))
      (node (ref "R51") (pin "2") (pinfunction "2_2") (pintype "passive"))
    )
    (net (code "64") (name "Net-(Q6-B)") (class "Default")
      (node (ref "Q6") (pin "1") (pinfunction "B_1") (pintype "passive"))
      (node (ref "Q6") (pin "2") (pinfunction "C_2") (pintype "passive"))
      (node (ref "R46") (pin "1") (pinfunction "1_1") (pintype "passive"))
      (node (ref "R47") (pin "1") (pinfunction "1_1") (pintype "passive"))
    )
    (net (code "65") (name "Net-(Q7-B)") (class "Default")
      (node (ref "C32") (pin "+") (pinfunction "+_+") (pintype "passive"))
      (node (ref "Q7") (pin "1") (pinfunction "B_1") (pintype "passive"))
      (node (ref "R47") (pin "2") (pinfunction "2_2") (pintype "passive"))
      (node (ref "R48") (pin "2") (pinfunction "2_2") (pintype "passive"))
    )
    (net (code "66") (name "Net-(Q7-C)") (class "Default")
      (node (ref "Q7") (pin "2") (pinfunction "C_2") (pintype "passive"))
      (node (ref "R52") (pin "1") (pinfunction "1_1") (pintype "passive"))
    )
    (net (code "67") (name "Net-(Q8-B)") (class "Default")
      (node (ref "Q8") (pin "1") (pinfunction "B_1") (pintype "passive"))
      (node (ref "R42") (pin "2") (pinfunction "2_2") (pintype "passive"))
      (node (ref "R43") (pin "1") (pinfunction "1_1") (pintype "passive"))
      (node (ref "R44") (pin "2") (pinfunction "2_2") (pintype "passive"))
    )
    (net (code "68") (name "Net-(Q9-B)") (class "Default")
      (node (ref "C35") (pin "2") (pinfunction "2_2") (pintype "passive"))
      (node (ref "C36") (pin "1") (pinfunction "1_1") (pintype "passive"))
      (node (ref "Q9") (pin "1") (pinfunction "B_1") (pintype "passive"))
      (node (ref "R58") (pin "1") (pinfunction "1_1") (pintype "passive"))
      (node (ref "R59") (pin "2") (pinfunction "2_2") (pintype "passive"))
    )
    (net (code "69") (name "Net-(Q9-C)") (class "Default")
      (node (ref "C34") (pin "2") (pinfunction "2_2") (pintype "passive"))
      (node (ref "Q9") (pin "2") (pinfunction "C_2") (pintype "passive"))
      (node (ref "R55") (pin "1") (pinfunction "1_1") (pintype "passive"))
      (node (ref "R57") (pin "1") (pinfunction "1_1") (pintype "passive"))
    )
    (net (code "70") (name "Net-(Q10-B)") (class "Default")
      (node (ref "C34") (pin "1") (pinfunction "1_1") (pintype "passive"))
      (node (ref "C37") (pin "1") (pinfunction "1_1") (pintype "passive"))
      (node (ref "Q10") (pin "1") (pinfunction "B_1") (pintype "passive"))
      (node (ref "R57") (pin "2") (pinfunction "2_2") (pintype "passive"))
      (node (ref "R60") (pin "2") (pinfunction "2_2") (pintype "passive"))
    )
    (net (code "71") (name "Net-(Q10-C)") (class "Default")
      (node (ref "C35") (pin "1") (pinfunction "1_1") (pintype "passive"))
      (node (ref "Q10") (pin "2") (pinfunction "C_2") (pintype "passive"))
      (node (ref "R56") (pin "1") (pinfunction "1_1") (pintype "passive"))
      (node (ref "R58") (pin "2") (pinfunction "2_2") (pintype "passive"))
    )
    (net (code "72") (name "Net-(Q10-E)") (class "Default")
      (node (ref "D7") (pin "A") (pinfunction "A_A") (pintype "passive"))
      (node (ref "D8") (pin "A") (pinfunction "A_A") (pintype "passive"))
      (node (ref "Q10") (pin "3") (pinfunction "E_3") (pintype "passive"))
      (node (ref "Q9") (pin "3") (pinfunction "E_3") (pintype "passive"))
      (node (ref "R61") (pin "1") (pinfunction "1_1") (pintype "passive"))
    )
    (net (code "73") (name "Net-(Q11-B)") (class "Default")
      (node (ref "Q11") (pin "1") (pinfunction "B_1") (pintype "passive"))
      (node (ref "R62") (pin "2") (pinfunction "2_2") (pintype "passive"))
    )
    (net (code "74") (name "Net-(R10-Pad2)") (class "Default")
      (node (ref "R10") (pin "2") (pinfunction "2_2") (pintype "passive"))
      (node (ref "VR5") (pin "2") (pinfunction "2_2") (pintype "passive"))
      (node (ref "VR5") (pin "3") (pinfunction "3_3") (pintype "passive"))
    )
    (net (code "75") (name "Net-(R42-Pad1)") (class "Default")
      (node (ref "R42") (pin "1") (pinfunction "1_1") (pintype "passive"))
      (node (ref "VR1") (pin "2") (pinfunction "2_2") (pintype "passive"))
    )
    (net (code "76") (name "Net-(R46-Pad2)") (class "Default")
      (node (ref "R46") (pin "2") (pinfunction "2_2") (pintype "passive"))
      (node (ref "VR7") (pin "2") (pinfunction "2_2") (pintype "passive"))
      (node (ref "VR7") (pin "3") (pinfunction "3_3") (pintype "passive"))
    )
    (net (code "77") (name "Net-(R48-Pad1)") (class "Default")
      (node (ref "R48") (pin "1") (pinfunction "1_1") (pintype "passive"))
      (node (ref "VR2") (pin "2") (pinfunction "2_2") (pintype "passive"))
    )
    (net (code "78") (name "Net-(R120-Pad1)") (class "Default")
      (node (ref "R120") (pin "1") (pinfunction "1_1") (pintype "passive"))
      (node (ref "VR3") (pin "3") (pinfunction "3_3") (pintype "passive"))
    )
    (net (code "79") (name "Net-(SW101-P)") (class "Default")
      (node (ref "R54") (pin "2") (pinfunction "2_2") (pintype "passive"))
      (node (ref "SW101") (pin "1") (pinfunction "P_1") (pintype "passive"))
    )
    (net (code "80") (name "OUT") (class "Default")
      (node (ref "C24") (pin "-") (pinfunction "-_-") (pintype "passive"))
      (node (ref "R33") (pin "1") (pinfunction "1_1") (pintype "passive"))
    )
    (net (code "81") (name "VA") (class "Default")
      (node (ref "C40") (pin "+") (pinfunction "+_+") (pintype "passive"))
      (node (ref "IC3") (pin "5") (pinfunction "5_5") (pintype "bidirectional"))
      (node (ref "IC4") (pin "1") (pinfunction "P$1_1") (pintype "bidirectional"))
      (node (ref "IC5") (pin "8") (pinfunction "V+_8") (pintype "power_in"))
      (node (ref "IC6") (pin "3") (pinfunction "VO_3") (pintype "passive"))
      (node (ref "Q5") (pin "3") (pinfunction "E_3") (pintype "passive"))
      (node (ref "Q8") (pin "2") (pinfunction "C_2") (pintype "passive"))
      (node (ref "R40") (pin "2") (pinfunction "2_2") (pintype "passive"))
      (node (ref "R43") (pin "2") (pinfunction "2_2") (pintype "passive"))
      (node (ref "R50") (pin "2") (pinfunction "2_2") (pintype "passive"))
      (node (ref "VR1") (pin "3") (pinfunction "3_3") (pintype "passive"))
      (node (ref "VR6") (pin "3") (pinfunction "3_3") (pintype "passive"))
      (node (ref "VR7") (pin "1") (pinfunction "1_1") (pintype "passive"))
    )
    (net (code "82") (name "VB") (class "Default")
      (node (ref "C25") (pin "+") (pinfunction "+_+") (pintype "passive"))
      (node (ref "IC1") (pin "3") (pinfunction "+IN_3") (pintype "input"))
      (node (ref "IC2") (pin "3") (pinfunction "+IN_3") (pintype "input"))
      (node (ref "R13") (pin "1") (pinfunction "1_1") (pintype "passive"))
      (node (ref "R19") (pin "1") (pinfunction "1_1") (pintype "passive"))
      (node (ref "R2") (pin "1") (pinfunction "1_1") (pintype "passive"))
      (node (ref "R27") (pin "1") (pinfunction "1_1") (pintype "passive"))
      (node (ref "R34") (pin "1") (pinfunction "1_1") (pintype "passive"))
      (node (ref "R35") (pin "2") (pinfunction "2_2") (pintype "passive"))
      (node (ref "R7") (pin "1") (pinfunction "1_1") (pintype "passive"))
    )
    (net (code "83") (name "unconnected-(IC4-P$6-Pad6)") (class "Default")
      (node (ref "IC4") (pin "6") (pinfunction "P$6_6") (pintype "bidirectional"))
    )
  )
)
